# MAX14830ETM.net
KiCad netlist of a schematic drawn in Altium Designer
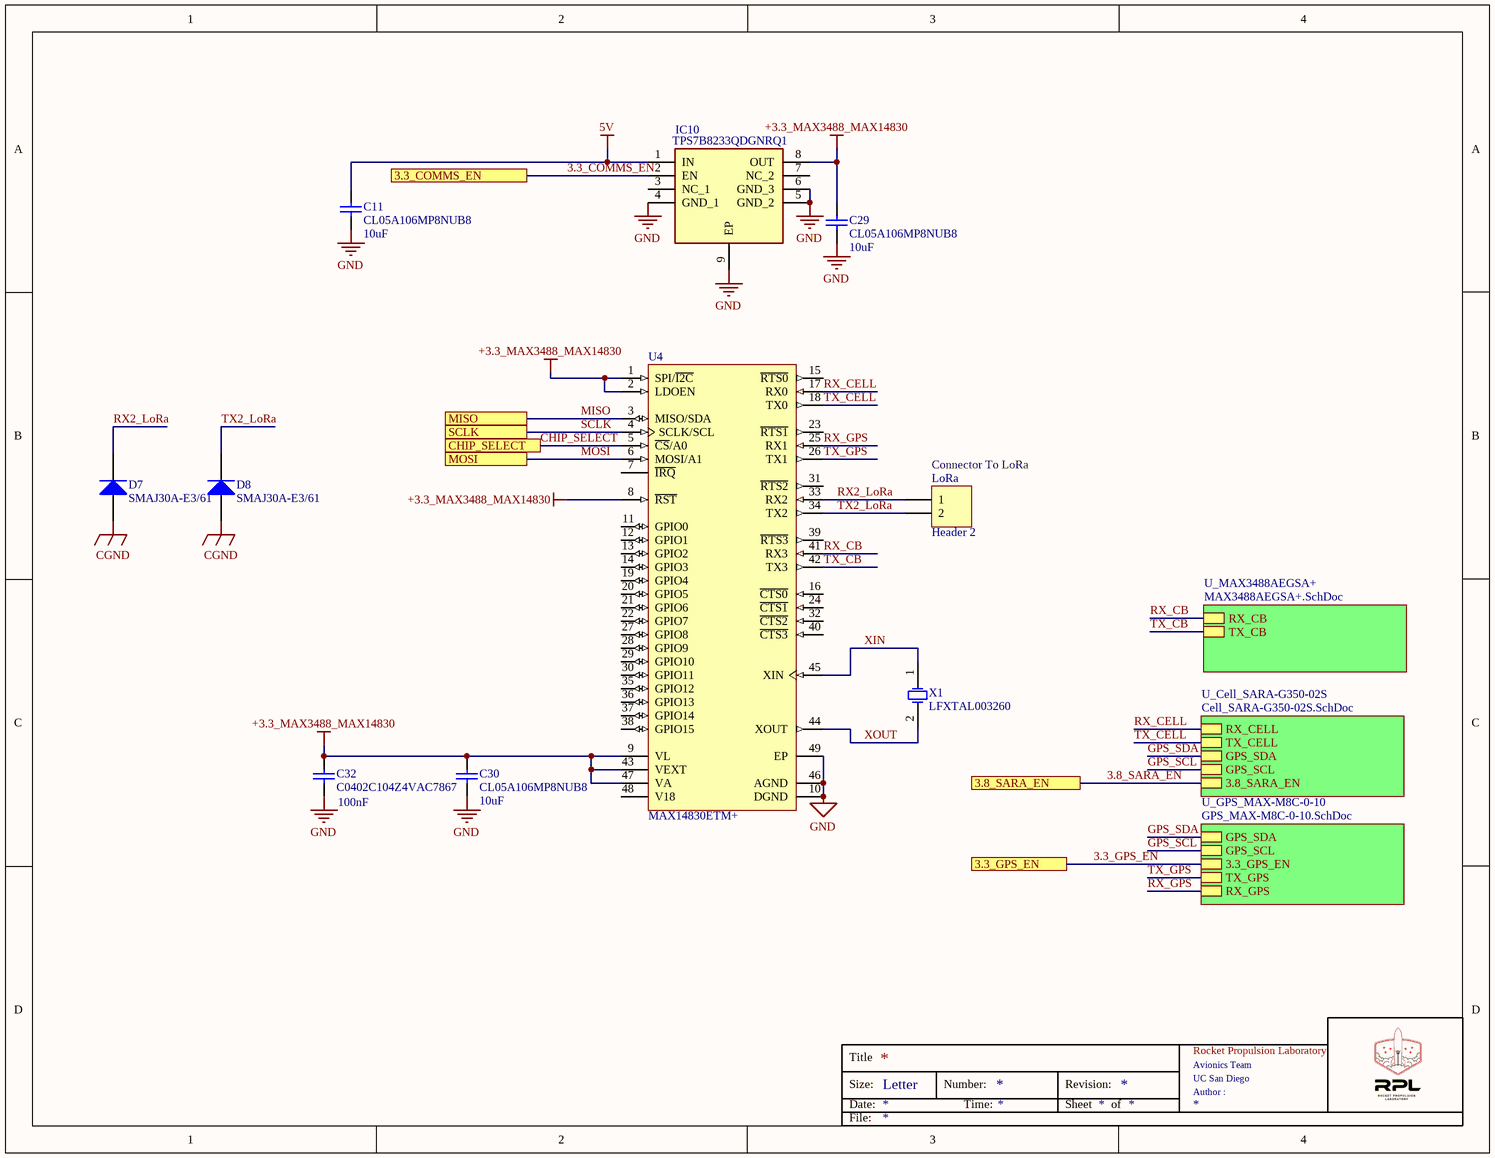
[diagram p0: MAX14830ETM+.SchDoc]

(export (version "E")
  (design (tool "Eeschema 10.0.6"))
  (components
    (comp (ref "C11")
      (value "CL05A106MP8NUB8")
      (footprint "0402")
      (description "Capacitor")
      (fields (field (name "ALTIUM_VALUE") "10uF") (field (name "PUBLISHER") "Altium Limited"))
      (libsource (lib "Miscellaneous Devices") (part "Cap"))
    )
    (comp (ref "C29")
      (value "CL05A106MP8NUB8")
      (footprint "0402")
      (description "Capacitor")
      (fields (field (name "ALTIUM_VALUE") "10uF") (field (name "PUBLISHER") "Altium Limited"))
      (libsource (lib "Miscellaneous Devices") (part "Cap"))
    )
    (comp (ref "C30")
      (value "CL05A106MP8NUB8")
      (footprint "0402")
      (description "Capacitor")
      (fields (field (name "ALTIUM_VALUE") "10uF") (field (name "PUBLISHER") "Altium Limited"))
      (libsource (lib "Miscellaneous Devices") (part "Cap"))
    )
    (comp (ref "C32")
      (value "C0402C104Z4VAC7867")
      (footprint "CAPC1005X60X30LL05T10")
      (fields (field (name "MANUFACTURER") "Kemet") (field (name "SPEC") "100nF"))
      (libsource (lib "Altium Content Vault") (part "CAP"))
    )
    (comp (ref "D7")
      (value "SMAJ30A-E3/61")
      (footprint "VISH-DO-214AC-2_N")
      (fields (field (name "MANUFACTURER") "Vishay Semiconductor"))
      (libsource (lib "Altium Content Vault") (part "VISH-K1A2-2"))
    )
    (comp (ref "D8")
      (value "SMAJ30A-E3/61")
      (footprint "VISH-DO-214AC-2_N")
      (fields (field (name "MANUFACTURER") "Vishay Semiconductor"))
      (libsource (lib "Altium Content Vault") (part "VISH-K1A2-2"))
    )
    (comp (ref "IC10")
      (value "TPS7B8233QDGNRQ1")
      (footprint "PcbLib1:SOP65P490X110-9N")
      (description "Integrated Circuit")
      (fields (field (name "MOUSER PART NUMBER") "595-TPS7B8233QDGNRQ1"))
      (libsource (lib "*") (part "TPS7B8233QDGNRQ1"))
    )
    (comp (ref "LoRa")
      (value "Header 2")
      (footprint "HDR1X2")
      (description "Header, 2-Pin")
      (fields (field (name "PUBLISHER") "Altium Limited"))
      (libsource (lib "Miscellaneous Connectors") (part "Header 2"))
    )
    (comp (ref "U4")
      (value "MAX14830ETM+")
      (footprint "T4877+3_M")
      (description "Quad Serial UART with 128-Word FIFO, 48-Pin TQFN, -40°C to +85°C, Pb-Free")
      (libsource (lib "Altium Content Vault") (part "MAX-MAX14830-SQ49"))
    )
    (comp (ref "X1")
      (value "LFXTAL003260")
      (footprint "ABRA-ABLS2-2_V")
      (fields (field (name "MANUFACTURER") "Abracon") (field (name "PARTNUMBER") "ABLS2-4.096MHZ-D4Y-T"))
      (libsource (lib "Altium Content Vault") (part "ABRA-XTAL_1-2-2"))
    )
  )
  (nets
    (net (code "1") (name "+3.3_MAX3488_MAX14830") (class "Default")
      (node (ref "C29") (pin "2") (pinfunction "2_2") (pintype "passive"))
      (node (ref "C30") (pin "2") (pinfunction "2_2") (pintype "passive"))
      (node (ref "C32") (pin "2") (pinfunction "2_2") (pintype "passive"))
      (node (ref "IC10") (pin "8") (pinfunction "OUT_8") (pintype "passive"))
      (node (ref "U4") (pin "1") (pinfunction "SPI/~{I2C}_1") (pintype "input"))
      (node (ref "U4") (pin "2") (pinfunction "LDOEN_2") (pintype "input"))
      (node (ref "U4") (pin "43") (pinfunction "VEXT_43") (pintype "power_in"))
      (node (ref "U4") (pin "47") (pinfunction "VA_47") (pintype "power_in"))
      (node (ref "U4") (pin "8") (pinfunction "~{RST}_8") (pintype "input"))
      (node (ref "U4") (pin "9") (pinfunction "VL_9") (pintype "power_in"))
    )
    (net (code "2") (name "/3.3_COMMS_EN") (class "Default")
      (node (ref "IC10") (pin "2") (pinfunction "EN_2") (pintype "passive"))
    )
    (net (code "5") (name "/CHIP_SELECT") (class "Default")
      (node (ref "U4") (pin "5") (pinfunction "~{CS}/A0_5") (pintype "input"))
    )
    (net (code "8") (name "/MISO") (class "Default")
      (node (ref "U4") (pin "3") (pinfunction "MISO/SDA_3") (pintype "bidirectional"))
    )
    (net (code "9") (name "/MOSI") (class "Default")
      (node (ref "U4") (pin "6") (pinfunction "MOSI/A1_6") (pintype "input"))
    )
    (net (code "10") (name "/RX2_LoRa") (class "Default")
      (node (ref "D7") (pin "1") (pinfunction "K_1") (pintype "passive"))
      (node (ref "LoRa") (pin "1") (pinfunction "1_1") (pintype "passive"))
      (node (ref "U4") (pin "33") (pinfunction "RX2_33") (pintype "input"))
    )
    (net (code "11") (name "/RX_CB") (class "Default")
      (node (ref "U4") (pin "41") (pinfunction "RX3_41") (pintype "input"))
    )
    (net (code "12") (name "/RX_CELL") (class "Default")
      (node (ref "U4") (pin "17") (pinfunction "RX0_17") (pintype "input"))
    )
    (net (code "13") (name "/RX_GPS") (class "Default")
      (node (ref "U4") (pin "25") (pinfunction "RX1_25") (pintype "input"))
    )
    (net (code "14") (name "/SCLK") (class "Default")
      (node (ref "U4") (pin "4") (pinfunction "SCLK/SCL_4") (pintype "input"))
    )
    (net (code "15") (name "/TX2_LoRa") (class "Default")
      (node (ref "D8") (pin "1") (pinfunction "K_1") (pintype "passive"))
      (node (ref "LoRa") (pin "2") (pinfunction "2_2") (pintype "passive"))
      (node (ref "U4") (pin "34") (pinfunction "TX2_34") (pintype "output"))
    )
    (net (code "16") (name "/TX_CB") (class "Default")
      (node (ref "U4") (pin "42") (pinfunction "TX3_42") (pintype "output"))
    )
    (net (code "17") (name "/TX_CELL") (class "Default")
      (node (ref "U4") (pin "18") (pinfunction "TX0_18") (pintype "output"))
    )
    (net (code "18") (name "/TX_GPS") (class "Default")
      (node (ref "U4") (pin "26") (pinfunction "TX1_26") (pintype "output"))
    )
    (net (code "19") (name "/XIN") (class "Default")
      (node (ref "U4") (pin "45") (pinfunction "XIN_45") (pintype "input"))
      (node (ref "X1") (pin "1") (pinfunction "X1_1") (pintype "passive"))
    )
    (net (code "20") (name "/XOUT") (class "Default")
      (node (ref "U4") (pin "44") (pinfunction "XOUT_44") (pintype "output"))
      (node (ref "X1") (pin "2") (pinfunction "X2_2") (pintype "passive"))
    )
    (net (code "21") (name "5V") (class "Default")
      (node (ref "C11") (pin "2") (pinfunction "2_2") (pintype "passive"))
      (node (ref "IC10") (pin "1") (pinfunction "IN_1") (pintype "passive"))
    )
    (net (code "22") (name "CGND") (class "Default")
      (node (ref "D7") (pin "2") (pinfunction "A_2") (pintype "passive"))
      (node (ref "D8") (pin "2") (pinfunction "A_2") (pintype "passive"))
    )
    (net (code "23") (name "GND") (class "Default")
      (node (ref "C11") (pin "1") (pinfunction "1_1") (pintype "passive"))
      (node (ref "C29") (pin "1") (pinfunction "1_1") (pintype "passive"))
      (node (ref "C30") (pin "1") (pinfunction "1_1") (pintype "passive"))
      (node (ref "C32") (pin "1") (pinfunction "1_1") (pintype "passive"))
      (node (ref "IC10") (pin "4") (pinfunction "GND_1_4") (pintype "passive"))
      (node (ref "IC10") (pin "5") (pinfunction "GND_2_5") (pintype "passive"))
      (node (ref "IC10") (pin "6") (pinfunction "GND_3_6") (pintype "passive"))
      (node (ref "IC10") (pin "9") (pinfunction "EP_9") (pintype "passive"))
      (node (ref "U4") (pin "10") (pinfunction "DGND_10") (pintype "power_in"))
      (node (ref "U4") (pin "46") (pinfunction "AGND_46") (pintype "power_in"))
      (node (ref "U4") (pin "49") (pinfunction "EP_49") (pintype "power_in"))
    )
    (net (code "24") (name "unconnected-(IC10-NC_1-Pad3)") (class "Default")
      (node (ref "IC10") (pin "3") (pinfunction "NC_1_3") (pintype "passive"))
    )
    (net (code "25") (name "unconnected-(IC10-NC_2-Pad7)") (class "Default")
      (node (ref "IC10") (pin "7") (pinfunction "NC_2_7") (pintype "passive"))
    )
    (net (code "26") (name "unconnected-(U4-GPIO0-Pad11)") (class "Default")
      (node (ref "U4") (pin "11") (pinfunction "GPIO0_11") (pintype "bidirectional"))
    )
    (net (code "27") (name "unconnected-(U4-GPIO1-Pad12)") (class "Default")
      (node (ref "U4") (pin "12") (pinfunction "GPIO1_12") (pintype "bidirectional"))
    )
    (net (code "28") (name "unconnected-(U4-GPIO2-Pad13)") (class "Default")
      (node (ref "U4") (pin "13") (pinfunction "GPIO2_13") (pintype "bidirectional"))
    )
    (net (code "29") (name "unconnected-(U4-GPIO3-Pad14)") (class "Default")
      (node (ref "U4") (pin "14") (pinfunction "GPIO3_14") (pintype "bidirectional"))
    )
    (net (code "30") (name "unconnected-(U4-GPIO4-Pad19)") (class "Default")
      (node (ref "U4") (pin "19") (pinfunction "GPIO4_19") (pintype "bidirectional"))
    )
    (net (code "31") (name "unconnected-(U4-GPIO5-Pad20)") (class "Default")
      (node (ref "U4") (pin "20") (pinfunction "GPIO5_20") (pintype "bidirectional"))
    )
    (net (code "32") (name "unconnected-(U4-GPIO6-Pad21)") (class "Default")
      (node (ref "U4") (pin "21") (pinfunction "GPIO6_21") (pintype "bidirectional"))
    )
    (net (code "33") (name "unconnected-(U4-GPIO7-Pad22)") (class "Default")
      (node (ref "U4") (pin "22") (pinfunction "GPIO7_22") (pintype "bidirectional"))
    )
    (net (code "34") (name "unconnected-(U4-GPIO8-Pad27)") (class "Default")
      (node (ref "U4") (pin "27") (pinfunction "GPIO8_27") (pintype "bidirectional"))
    )
    (net (code "35") (name "unconnected-(U4-GPIO9-Pad28)") (class "Default")
      (node (ref "U4") (pin "28") (pinfunction "GPIO9_28") (pintype "bidirectional"))
    )
    (net (code "36") (name "unconnected-(U4-GPIO10-Pad29)") (class "Default")
      (node (ref "U4") (pin "29") (pinfunction "GPIO10_29") (pintype "bidirectional"))
    )
    (net (code "37") (name "unconnected-(U4-GPIO11-Pad30)") (class "Default")
      (node (ref "U4") (pin "30") (pinfunction "GPIO11_30") (pintype "bidirectional"))
    )
    (net (code "38") (name "unconnected-(U4-GPIO12-Pad35)") (class "Default")
      (node (ref "U4") (pin "35") (pinfunction "GPIO12_35") (pintype "bidirectional"))
    )
    (net (code "39") (name "unconnected-(U4-GPIO13-Pad36)") (class "Default")
      (node (ref "U4") (pin "36") (pinfunction "GPIO13_36") (pintype "bidirectional"))
    )
    (net (code "40") (name "unconnected-(U4-GPIO14-Pad37)") (class "Default")
      (node (ref "U4") (pin "37") (pinfunction "GPIO14_37") (pintype "bidirectional"))
    )
    (net (code "41") (name "unconnected-(U4-GPIO15-Pad38)") (class "Default")
      (node (ref "U4") (pin "38") (pinfunction "GPIO15_38") (pintype "bidirectional"))
    )
    (net (code "42") (name "unconnected-(U4-V18-Pad48)") (class "Default")
      (node (ref "U4") (pin "48") (pinfunction "V18_48") (pintype "power_in"))
    )
    (net (code "43") (name "unconnected-(U4-~{CTS0}-Pad16)") (class "Default")
      (node (ref "U4") (pin "16") (pinfunction "~{CTS0}_16") (pintype "input"))
    )
    (net (code "44") (name "unconnected-(U4-~{CTS1}-Pad24)") (class "Default")
      (node (ref "U4") (pin "24") (pinfunction "~{CTS1}_24") (pintype "input"))
    )
    (net (code "45") (name "unconnected-(U4-~{CTS2}-Pad32)") (class "Default")
      (node (ref "U4") (pin "32") (pinfunction "~{CTS2}_32") (pintype "input"))
    )
    (net (code "46") (name "unconnected-(U4-~{CTS3}-Pad40)") (class "Default")
      (node (ref "U4") (pin "40") (pinfunction "~{CTS3}_40") (pintype "input"))
    )
    (net (code "47") (name "unconnected-(U4-~{IRQ}-Pad7)") (class "Default")
      (node (ref "U4") (pin "7") (pinfunction "~{IRQ}_7") (pintype "open_collector"))
    )
    (net (code "48") (name "unconnected-(U4-~{RTS0}-Pad15)") (class "Default")
      (node (ref "U4") (pin "15") (pinfunction "~{RTS0}_15") (pintype "output"))
    )
    (net (code "49") (name "unconnected-(U4-~{RTS1}-Pad23)") (class "Default")
      (node (ref "U4") (pin "23") (pinfunction "~{RTS1}_23") (pintype "output"))
    )
    (net (code "50") (name "unconnected-(U4-~{RTS2}-Pad31)") (class "Default")
      (node (ref "U4") (pin "31") (pinfunction "~{RTS2}_31") (pintype "output"))
    )
    (net (code "51") (name "unconnected-(U4-~{RTS3}-Pad39)") (class "Default")
      (node (ref "U4") (pin "39") (pinfunction "~{RTS3}_39") (pintype "output"))
    )
  )
)
